# Sheet3.net
KiCad netlist of a schematic drawn in Altium Designer
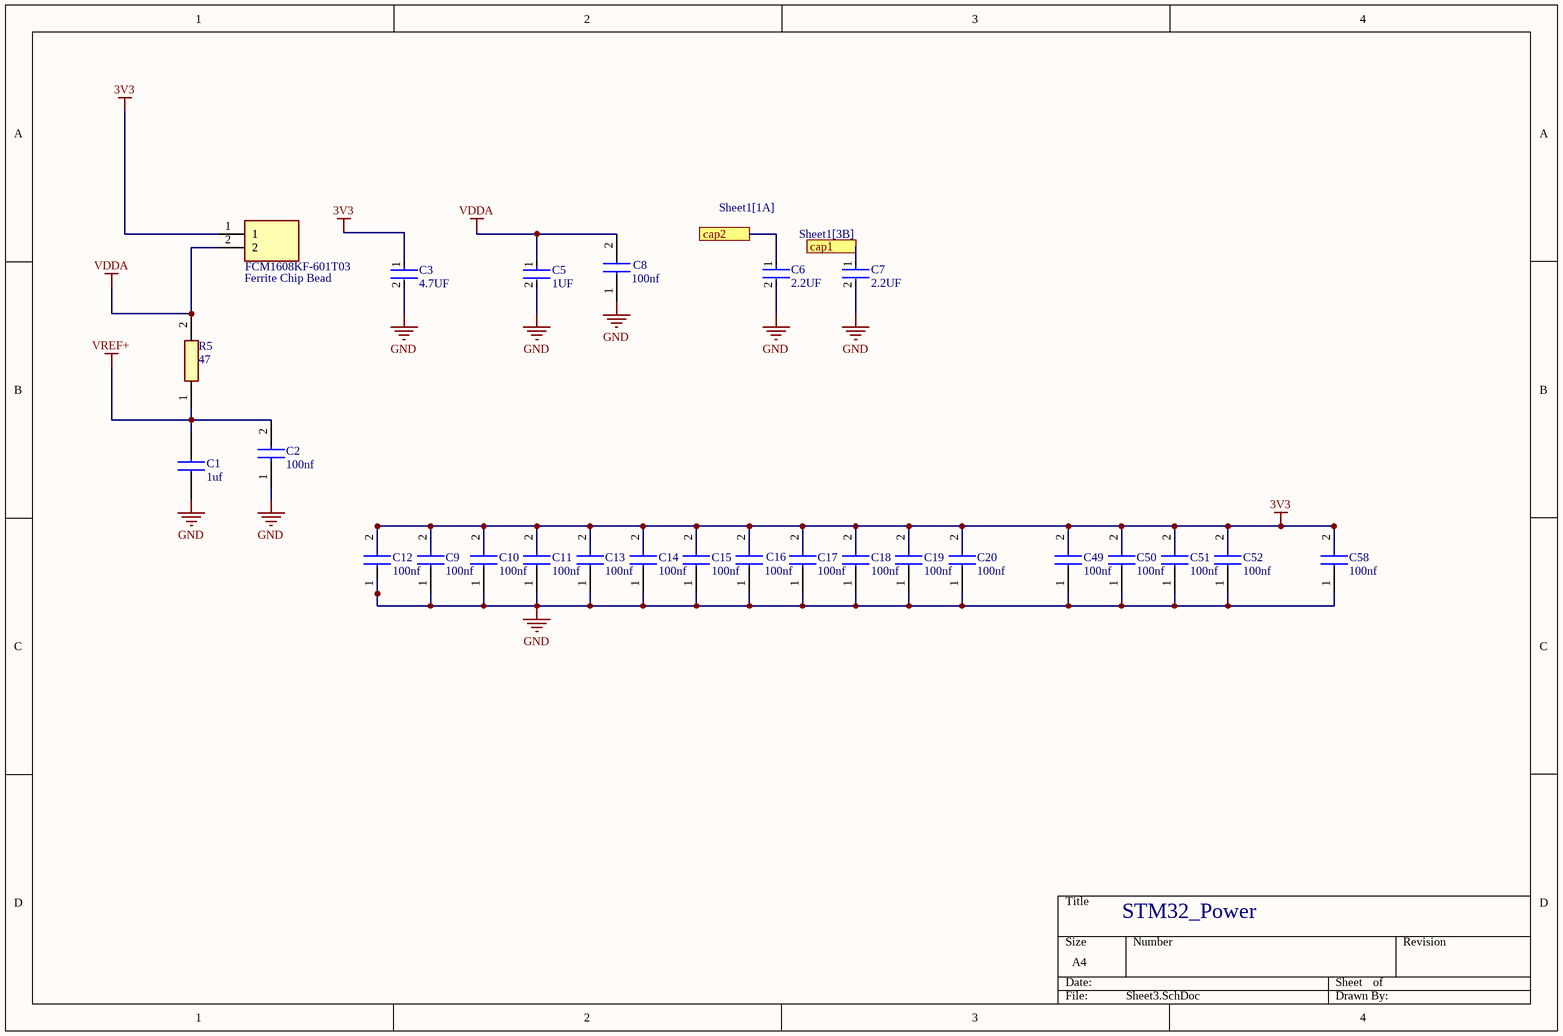
[diagram p0: Sheet3.SchDoc]

(export (version "E")
  (design (tool "Eeschema 10.0.6"))
  (components
    (comp (ref "C1")
      (value "1uf")
      (footprint "CAPC1608X95N")
      (fields (field (name "MANUFACTURER_PART_NUMBER") "0603X105K250CT"))
      (libsource (lib "0603X105K250CT") (part "0603X105K250CT"))
    )
    (comp (ref "C2")
      (value "100nf")
      (footprint "SamacSys:CAPC1608X95N")
      (description "Capacitor")
      (fields (field (name "MANUFACTURER_PART_NUMBER") "VJ0603Y104KXACW1BC"))
      (libsource (lib "*") (part "VJ0603Y104KXACW1BC"))
    )
    (comp (ref "C3")
      (value "4.7UF")
      (footprint "FP-CL10-IPC_A")
      (description "Cap Ceramic 2.2uF 10V X7R ±10% Pad SMD 0603 +125°C T/R")
      (fields (field (name "TOLERANCE") "10%"))
      (libsource (lib "Altium Content Vault") (part "b4654b650e69147ec39a6b967a45e02"))
    )
    (comp (ref "C5")
      (value "1UF")
      (footprint "FP-CL10-IPC_A")
      (description "Cap Ceramic 2.2uF 10V X7R ±10% Pad SMD 0603 +125°C T/R")
      (fields (field (name "TOLERANCE") "10%"))
      (libsource (lib "Altium Content Vault") (part "b4654b650e69147ec39a6b967a45e02"))
    )
    (comp (ref "C6")
      (value "2.2UF")
      (footprint "FP-CL10-IPC_A")
      (description "Cap Ceramic 2.2uF 10V X7R ±10% Pad SMD 0603 +125°C T/R")
      (fields (field (name "TOLERANCE") "10%"))
      (libsource (lib "Altium Content Vault") (part "b4654b650e69147ec39a6b967a45e02"))
    )
    (comp (ref "C7")
      (value "2.2UF")
      (footprint "FP-CL10-IPC_A")
      (description "Cap Ceramic 2.2uF 10V X7R ±10% Pad SMD 0603 +125°C T/R")
      (fields (field (name "TOLERANCE") "10%"))
      (libsource (lib "Altium Content Vault") (part "b4654b650e69147ec39a6b967a45e02"))
    )
    (comp (ref "C8")
      (value "100nf")
      (footprint "SamacSys:CAPC1608X95N")
      (description "Capacitor")
      (fields (field (name "MANUFACTURER_PART_NUMBER") "VJ0603Y104KXACW1BC"))
      (libsource (lib "*") (part "VJ0603Y104KXACW1BC"))
    )
    (comp (ref "C9")
      (value "100nf")
      (footprint "SamacSys:CAPC1608X95N")
      (description "Capacitor")
      (fields (field (name "MANUFACTURER_PART_NUMBER") "VJ0603Y104KXACW1BC"))
      (libsource (lib "*") (part "VJ0603Y104KXACW1BC"))
    )
    (comp (ref "C10")
      (value "100nf")
      (footprint "SamacSys:CAPC1608X95N")
      (description "Capacitor")
      (fields (field (name "MANUFACTURER_PART_NUMBER") "VJ0603Y104KXACW1BC"))
      (libsource (lib "*") (part "VJ0603Y104KXACW1BC"))
    )
    (comp (ref "C11")
      (value "100nf")
      (footprint "SamacSys:CAPC1608X95N")
      (description "Capacitor")
      (fields (field (name "MANUFACTURER_PART_NUMBER") "VJ0603Y104KXACW1BC"))
      (libsource (lib "*") (part "VJ0603Y104KXACW1BC"))
    )
    (comp (ref "C12")
      (value "100nf")
      (footprint "SamacSys:CAPC1608X95N")
      (description "Capacitor")
      (fields (field (name "MANUFACTURER_PART_NUMBER") "VJ0603Y104KXACW1BC"))
      (libsource (lib "*") (part "VJ0603Y104KXACW1BC"))
    )
    (comp (ref "C13")
      (value "100nf")
      (footprint "SamacSys:CAPC1608X95N")
      (description "Capacitor")
      (fields (field (name "MANUFACTURER_PART_NUMBER") "VJ0603Y104KXACW1BC"))
      (libsource (lib "*") (part "VJ0603Y104KXACW1BC"))
    )
    (comp (ref "C14")
      (value "100nf")
      (footprint "SamacSys:CAPC1608X95N")
      (description "Capacitor")
      (fields (field (name "MANUFACTURER_PART_NUMBER") "VJ0603Y104KXACW1BC"))
      (libsource (lib "*") (part "VJ0603Y104KXACW1BC"))
    )
    (comp (ref "C15")
      (value "100nf")
      (footprint "SamacSys:CAPC1608X95N")
      (description "Capacitor")
      (fields (field (name "MANUFACTURER_PART_NUMBER") "VJ0603Y104KXACW1BC"))
      (libsource (lib "*") (part "VJ0603Y104KXACW1BC"))
    )
    (comp (ref "C16")
      (value "100nf")
      (footprint "SamacSys:CAPC1608X95N")
      (description "Capacitor")
      (fields (field (name "MANUFACTURER_PART_NUMBER") "VJ0603Y104KXACW1BC"))
      (libsource (lib "*") (part "VJ0603Y104KXACW1BC"))
    )
    (comp (ref "C17")
      (value "100nf")
      (footprint "SamacSys:CAPC1608X95N")
      (description "Capacitor")
      (fields (field (name "MANUFACTURER_PART_NUMBER") "VJ0603Y104KXACW1BC"))
      (libsource (lib "*") (part "VJ0603Y104KXACW1BC"))
    )
    (comp (ref "C18")
      (value "100nf")
      (footprint "SamacSys:CAPC1608X95N")
      (description "Capacitor")
      (fields (field (name "MANUFACTURER_PART_NUMBER") "VJ0603Y104KXACW1BC"))
      (libsource (lib "*") (part "VJ0603Y104KXACW1BC"))
    )
    (comp (ref "C19")
      (value "100nf")
      (footprint "SamacSys:CAPC1608X95N")
      (description "Capacitor")
      (fields (field (name "MANUFACTURER_PART_NUMBER") "VJ0603Y104KXACW1BC"))
      (libsource (lib "*") (part "VJ0603Y104KXACW1BC"))
    )
    (comp (ref "C20")
      (value "100nf")
      (footprint "SamacSys:CAPC1608X95N")
      (description "Capacitor")
      (fields (field (name "MANUFACTURER_PART_NUMBER") "VJ0603Y104KXACW1BC"))
      (libsource (lib "*") (part "VJ0603Y104KXACW1BC"))
    )
    (comp (ref "C49")
      (value "100nf")
      (footprint "SamacSys:CAPC1608X95N")
      (description "Capacitor")
      (fields (field (name "MANUFACTURER_PART_NUMBER") "VJ0603Y104KXACW1BC"))
      (libsource (lib "*") (part "VJ0603Y104KXACW1BC"))
    )
    (comp (ref "C50")
      (value "100nf")
      (footprint "SamacSys:CAPC1608X95N")
      (description "Capacitor")
      (fields (field (name "MANUFACTURER_PART_NUMBER") "VJ0603Y104KXACW1BC"))
      (libsource (lib "*") (part "VJ0603Y104KXACW1BC"))
    )
    (comp (ref "C51")
      (value "100nf")
      (footprint "SamacSys:CAPC1608X95N")
      (description "Capacitor")
      (fields (field (name "MANUFACTURER_PART_NUMBER") "VJ0603Y104KXACW1BC"))
      (libsource (lib "*") (part "VJ0603Y104KXACW1BC"))
    )
    (comp (ref "C52")
      (value "100nf")
      (footprint "SamacSys:CAPC1608X95N")
      (description "Capacitor")
      (fields (field (name "MANUFACTURER_PART_NUMBER") "VJ0603Y104KXACW1BC"))
      (libsource (lib "*") (part "VJ0603Y104KXACW1BC"))
    )
    (comp (ref "C58")
      (value "100nf")
      (footprint "SamacSys:CAPC1608X95N")
      (description "Capacitor")
      (fields (field (name "MANUFACTURER_PART_NUMBER") "VJ0603Y104KXACW1BC"))
      (libsource (lib "*") (part "VJ0603Y104KXACW1BC"))
    )
    (comp (ref "Ferrite Chip Bead")
      (value "FCM1608KF-601T03")
      (footprint "SamacSys:BEADC1608X95N")
      (description "Ferrite Bead")
      (libsource (lib "*") (part "FCM1608KF-601T03"))
    )
    (comp (ref "R5")
      (value "47")
      (footprint "SamacSys:RESC1608X55N")
      (description "Resistor")
      (fields
        (field (name "MANUFACTURER_PART_NUMBER") "RC0603FR-071KL")
        (field (name "MOUSER PART NUMBER") "603-RC0603FR-071KL")
      )
      (libsource (lib "*") (part "RC0603FR-071KL"))
    )
  )
  (nets
    (net (code "1") (name "/cap1") (class "Default")
      (node (ref "C7") (pin "1") (pinfunction "1_1") (pintype "passive"))
    )
    (net (code "2") (name "/cap2") (class "Default")
      (node (ref "C6") (pin "1") (pinfunction "1_1") (pintype "passive"))
    )
    (net (code "3") (name "3V3") (class "Default")
      (node (ref "C10") (pin "2") (pinfunction "2_2") (pintype "passive"))
      (node (ref "C11") (pin "2") (pinfunction "2_2") (pintype "passive"))
      (node (ref "C12") (pin "2") (pinfunction "2_2") (pintype "passive"))
      (node (ref "C13") (pin "2") (pinfunction "2_2") (pintype "passive"))
      (node (ref "C14") (pin "2") (pinfunction "2_2") (pintype "passive"))
      (node (ref "C15") (pin "2") (pinfunction "2_2") (pintype "passive"))
      (node (ref "C16") (pin "2") (pinfunction "2_2") (pintype "passive"))
      (node (ref "C17") (pin "2") (pinfunction "2_2") (pintype "passive"))
      (node (ref "C18") (pin "2") (pinfunction "2_2") (pintype "passive"))
      (node (ref "C19") (pin "2") (pinfunction "2_2") (pintype "passive"))
      (node (ref "C20") (pin "2") (pinfunction "2_2") (pintype "passive"))
      (node (ref "C3") (pin "1") (pinfunction "1_1") (pintype "passive"))
      (node (ref "C49") (pin "2") (pinfunction "2_2") (pintype "passive"))
      (node (ref "C50") (pin "2") (pinfunction "2_2") (pintype "passive"))
      (node (ref "C51") (pin "2") (pinfunction "2_2") (pintype "passive"))
      (node (ref "C52") (pin "2") (pinfunction "2_2") (pintype "passive"))
      (node (ref "C58") (pin "2") (pinfunction "2_2") (pintype "passive"))
      (node (ref "C9") (pin "2") (pinfunction "2_2") (pintype "passive"))
      (node (ref "Ferrite Chip Bead") (pin "1") (pinfunction "1_1") (pintype "passive"))
    )
    (net (code "4") (name "GND") (class "Default")
      (node (ref "C1") (pin "1") (pinfunction "1_1") (pintype "passive"))
      (node (ref "C10") (pin "1") (pinfunction "1_1") (pintype "passive"))
      (node (ref "C11") (pin "1") (pinfunction "1_1") (pintype "passive"))
      (node (ref "C12") (pin "1") (pinfunction "1_1") (pintype "passive"))
      (node (ref "C13") (pin "1") (pinfunction "1_1") (pintype "passive"))
      (node (ref "C14") (pin "1") (pinfunction "1_1") (pintype "passive"))
      (node (ref "C15") (pin "1") (pinfunction "1_1") (pintype "passive"))
      (node (ref "C16") (pin "1") (pinfunction "1_1") (pintype "passive"))
      (node (ref "C17") (pin "1") (pinfunction "1_1") (pintype "passive"))
      (node (ref "C18") (pin "1") (pinfunction "1_1") (pintype "passive"))
      (node (ref "C19") (pin "1") (pinfunction "1_1") (pintype "passive"))
      (node (ref "C2") (pin "1") (pinfunction "1_1") (pintype "passive"))
      (node (ref "C20") (pin "1") (pinfunction "1_1") (pintype "passive"))
      (node (ref "C3") (pin "2") (pinfunction "2_2") (pintype "passive"))
      (node (ref "C49") (pin "1") (pinfunction "1_1") (pintype "passive"))
      (node (ref "C5") (pin "2") (pinfunction "2_2") (pintype "passive"))
      (node (ref "C50") (pin "1") (pinfunction "1_1") (pintype "passive"))
      (node (ref "C51") (pin "1") (pinfunction "1_1") (pintype "passive"))
      (node (ref "C52") (pin "1") (pinfunction "1_1") (pintype "passive"))
      (node (ref "C58") (pin "1") (pinfunction "1_1") (pintype "passive"))
      (node (ref "C6") (pin "2") (pinfunction "2_2") (pintype "passive"))
      (node (ref "C7") (pin "2") (pinfunction "2_2") (pintype "passive"))
      (node (ref "C8") (pin "1") (pinfunction "1_1") (pintype "passive"))
      (node (ref "C9") (pin "1") (pinfunction "1_1") (pintype "passive"))
    )
    (net (code "5") (name "VDDA") (class "Default")
      (node (ref "C5") (pin "1") (pinfunction "1_1") (pintype "passive"))
      (node (ref "C8") (pin "2") (pinfunction "2_2") (pintype "passive"))
      (node (ref "Ferrite Chip Bead") (pin "2") (pinfunction "2_2") (pintype "passive"))
      (node (ref "R5") (pin "2") (pinfunction "2_2") (pintype "passive"))
    )
    (net (code "6") (name "VREF+") (class "Default")
      (node (ref "C1") (pin "2") (pinfunction "2_2") (pintype "passive"))
      (node (ref "C2") (pin "2") (pinfunction "2_2") (pintype "passive"))
      (node (ref "R5") (pin "1") (pinfunction "1_1") (pintype "passive"))
    )
  )
)
